# LED-Meter.net
KiCad netlist of a schematic drawn in Altium Designer
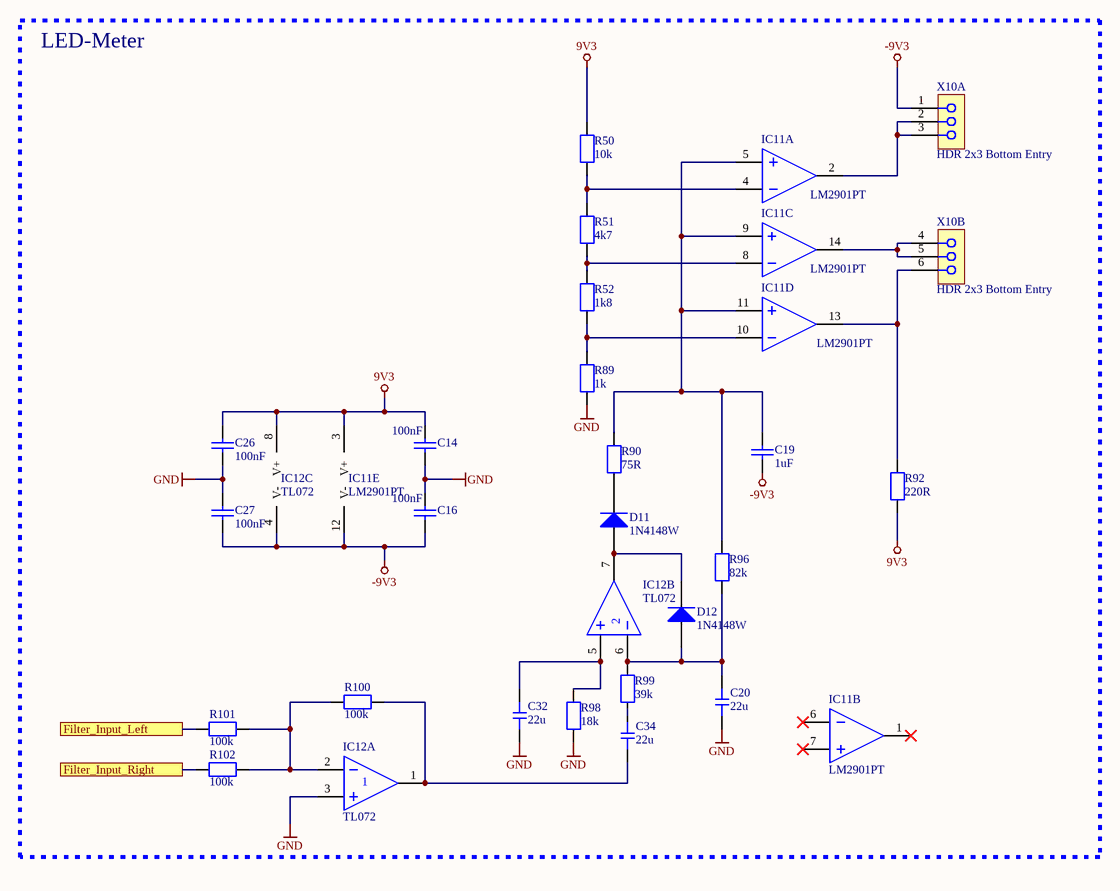
[diagram p0: LED-Meter.SchDoc]

(export (version "E")
  (design (tool "Eeschema 10.0.6"))
  (components
    (comp (ref "C14")
      (value "100nF")
      (footprint "CAPC1608X95N")
      (description "Multilayer Ceramic Capacitors MLCC - SMD/SMT, 100nF")
      (fields
        (field (name "MANUFACTURER") "YAGEO")
        (field (name "MANUFACTURER PART NUMBER") "CC0603KRX7R9BB104")
      )
      (libsource (lib "Caps") (part "CAP_100nF_0603"))
    )
    (comp (ref "C16")
      (value "100nF")
      (footprint "CAPC1608X95N")
      (description "Multilayer Ceramic Capacitors MLCC - SMD/SMT, 100nF")
      (fields
        (field (name "MANUFACTURER") "YAGEO")
        (field (name "MANUFACTURER PART NUMBER") "CC0603KRX7R9BB104")
      )
      (libsource (lib "Caps") (part "CAP_100nF_0603"))
    )
    (comp (ref "C19")
      (value "1uF")
      (footprint "CAPC2012X145N")
      (description "Multilayer Ceramic Capacitors MLCC - SMD/SMT, 1uF")
      (fields
        (field (name "MANUFACTURER") "Samsung Electro-Mechanics")
        (field (name "MANUFACTURER PART NUMBER") "CL21B105KBFNNNE")
      )
      (libsource (lib "Caps") (part "CAP_1uF_0805"))
    )
    (comp (ref "C20")
      (value "22u")
      (footprint "CAPC2012X145N")
      (description "SMD, 22 µF, 35 V, 0805 [metric 2012], ± 20%, X5R, C Series TDK")
      (fields
        (field (name "MANUFACTURER") "TDK")
        (field (name "MANUFACTURER PART NUMBER") "C2012X5R1V226M125AC")
      )
      (libsource (lib "Caps") (part "CAP_22u_35V_0805"))
    )
    (comp (ref "C26")
      (value "100nF")
      (footprint "CAPC1608X95N")
      (description "Multilayer Ceramic Capacitors MLCC - SMD/SMT, 100nF")
      (fields
        (field (name "MANUFACTURER") "YAGEO")
        (field (name "MANUFACTURER PART NUMBER") "CC0603KRX7R9BB104")
      )
      (libsource (lib "Caps") (part "CAP_100nF_0603"))
    )
    (comp (ref "C27")
      (value "100nF")
      (footprint "CAPC1608X95N")
      (description "Multilayer Ceramic Capacitors MLCC - SMD/SMT, 100nF")
      (fields
        (field (name "MANUFACTURER") "YAGEO")
        (field (name "MANUFACTURER PART NUMBER") "CC0603KRX7R9BB104")
      )
      (libsource (lib "Caps") (part "CAP_100nF_0603"))
    )
    (comp (ref "C32")
      (value "22u")
      (footprint "CAPC2012X145N")
      (description "SMD, 22 µF, 35 V, 0805 [metric 2012], ± 20%, X5R, C Series TDK")
      (fields
        (field (name "MANUFACTURER") "TDK")
        (field (name "MANUFACTURER PART NUMBER") "C2012X5R1V226M125AC")
      )
      (libsource (lib "Caps") (part "CAP_22u_35V_0805"))
    )
    (comp (ref "C34")
      (value "22u")
      (footprint "CAPC2012X145N")
      (description "SMD, 22 µF, 35 V, 0805 [metric 2012], ± 20%, X5R, C Series TDK")
      (fields
        (field (name "MANUFACTURER") "TDK")
        (field (name "MANUFACTURER PART NUMBER") "C2012X5R1V226M125AC")
      )
      (libsource (lib "Caps") (part "CAP_22u_35V_0805"))
    )
    (comp (ref "D11")
      (value "1N4148W")
      (footprint "SOD-123")
      (description "75V 150mA 1.25V @ 150mA 4ns SOD-123 Switching Diode RoHS")
      (fields (field (name "MANUFACTURER") "ST(Semtech)"))
      (libsource (lib "Diodes") (part "1N4148W"))
    )
    (comp (ref "D12")
      (value "1N4148W")
      (footprint "SOD-123")
      (description "75V 150mA 1.25V @ 150mA 4ns SOD-123 Switching Diode RoHS")
      (fields (field (name "MANUFACTURER") "ST(Semtech)"))
      (libsource (lib "Diodes") (part "1N4148W"))
    )
    (comp (ref "IC11")
      (value "LM2901PT")
      (footprint "TSOP65P640X105-14N")
      (description "Analog Comparators Lo-Pwr Quad Voltage")
      (fields (field (name "MANUFACTURER") "STMicroelectronics"))
      (libsource (lib "ICs") (part "IC_LM2901PT"))
    )
    (comp (ref "IC12")
      (value "TL072")
      (footprint "SOIC127P600X175-8N")
      (description "Operational Amplifiers - Op Amps Dual JFET Op Amp")
      (fields
        (field (name "MANUFACTURER") "Texas Instruments")
        (field (name "MANUFACTURER PART NUMBER") "TL072CDR")
      )
      (libsource (lib "ICs") (part "IC_TL072"))
    )
    (comp (ref "R50")
      (value "10k")
      (footprint "RESC2012X70N")
      (description "Thick Film Resistors - SMD 1/8watt 10Kohms 1% 100ppm")
      (fields
        (field (name "MANUFACTURER") "Vishay / Dale")
        (field (name "MANUFACTURER PART NUMBER") "CRCW080510K0FKEA")
      )
      (libsource (lib "Resistors") (part "RES_10k_0805"))
    )
    (comp (ref "R51")
      (value "4k7")
      (footprint "RESC2012X70N")
      (description "Thick Film Resistors - SMD 1/8Watt 4.7Kohms 1% Commercial Use")
      (fields
        (field (name "MANUFACTURER") "Vishay / Dale")
        (field (name "MANUFACTURER PART NUMBER") "CRCW08054K70FKEAC")
      )
      (libsource (lib "Resistors") (part "RES_4k7_0805"))
    )
    (comp (ref "R52")
      (value "1k8")
      (footprint "RESC2012X70N")
      (description "Thick Film Resistors - SMD 1/8Watt 1.8Kohms 1% Commercial Use")
      (fields
        (field (name "MANUFACTURER") "Vishay / Dale")
        (field (name "MANUFACTURER PART NUMBER") "CRCW08051K80FKEAC")
      )
      (libsource (lib "Resistors") (part "RES_1k8_0805"))
    )
    (comp (ref "R89")
      (value "1k")
      (footprint "RESC2012X70N")
      (description "Thick Film Resistors - SMD 1/8watt 1Kohms 1% 100ppm")
      (fields
        (field (name "MANUFACTURER") "Vishay / Dale")
        (field (name "MANUFACTURER PART NUMBER") "CRCW08051K00FKEA")
      )
      (libsource (lib "Resistors") (part "RES_1k_0805"))
    )
    (comp (ref "R90")
      (value "75R")
      (footprint "RESC2012X70N")
      (description "Thick Film Resistors - SMD 75 Ohms 125 mW 0805 1%")
      (fields
        (field (name "MANUFACTURER") "YAGEO")
        (field (name "MANUFACTURER PART NUMBER") "RC0805FR-0775RL")
      )
      (libsource (lib "Resistors") (part "RES_75R_0805"))
    )
    (comp (ref "R92")
      (value "220R")
      (footprint "RESC2012X70N")
      (description "Thick Film Resistors - SMD 1/8watt 220ohms 1% 100ppm")
      (fields
        (field (name "MANUFACTURER") "Vishay / Dale")
        (field (name "MANUFACTURER PART NUMBER") "CRCW0805220RFKEA")
      )
      (libsource (lib "Resistors") (part "RES_220R_0805"))
    )
    (comp (ref "R96")
      (value "82k")
      (footprint "RESC2012X70N")
      (description "Thick Film Resistors - SMD 82 kOhms 125 mW 0805 1%")
      (fields
        (field (name "MANUFACTURER") "YAGEO")
        (field (name "MANUFACTURER PART NUMBER") "RC0805FR-0782KL")
      )
      (libsource (lib "Resistors") (part "RES_82k_0805"))
    )
    (comp (ref "R98")
      (value "18k")
      (footprint "RESC2012X70N")
      (description "Thick Film Resistors - SMD 18kOhms 1/8W 0805 1%")
      (fields
        (field (name "MANUFACTURER") "YAGEO")
        (field (name "MANUFACTURER PART NUMBER") "RC0805FR-1018KL")
      )
      (libsource (lib "Resistors") (part "RES_18k_0805"))
    )
    (comp (ref "R99")
      (value "39k")
      (footprint "RESC2012X70N")
      (description "Thick Film Resistors - SMD 39 kOhms 125 mW 0805 1%")
      (fields
        (field (name "MANUFACTURER") "YAGEO")
        (field (name "MANUFACTURER PART NUMBER") "RC0805FR-0739KL")
      )
      (libsource (lib "Resistors") (part "RES_39k_0805"))
    )
    (comp (ref "R100")
      (value "100k")
      (footprint "RESC2012X70N")
      (description "Thick Film Resistors - SMD 1/8watt 100Kohms 1% 100ppm")
      (fields
        (field (name "MANUFACTURER") "Vishay / Dale")
        (field (name "MANUFACTURER PART NUMBER") "CRCW0805100KFKEA")
      )
      (libsource (lib "Resistors") (part "RES_100k_0805"))
    )
    (comp (ref "R101")
      (value "100k")
      (footprint "RESC2012X70N")
      (description "Thick Film Resistors - SMD 1/8watt 100Kohms 1% 100ppm")
      (fields
        (field (name "MANUFACTURER") "Vishay / Dale")
        (field (name "MANUFACTURER PART NUMBER") "CRCW0805100KFKEA")
      )
      (libsource (lib "Resistors") (part "RES_100k_0805"))
    )
    (comp (ref "R102")
      (value "100k")
      (footprint "RESC2012X70N")
      (description "Thick Film Resistors - SMD 1/8watt 100Kohms 1% 100ppm")
      (fields
        (field (name "MANUFACTURER") "Vishay / Dale")
        (field (name "MANUFACTURER PART NUMBER") "CRCW0805100KFKEA")
      )
      (libsource (lib "Resistors") (part "RES_100k_0805"))
    )
    (comp (ref "X10")
      (value "HDR 2x3 Bottom Entry")
      (footprint "613006216921-poti")
      (fields (field (name "MANUFACTURER") "WE") (field (name "MANUFACTURER PART NUMBER") "613004216921"))
      (libsource (lib "Connectors") (part "CON_SOCKET_2x3_Poti"))
    )
  )
  (nets
    (net (code "1") (name "-9V3") (class "Default")
      (node (ref "C16") (pin "1") (pinfunction "1_1") (pintype "passive"))
      (node (ref "C19") (pin "1") (pinfunction "1_1") (pintype "passive"))
      (node (ref "C27") (pin "2") (pinfunction "2_2") (pintype "passive"))
      (node (ref "IC11") (pin "12") (pinfunction "V-_12") (pintype "power_in"))
      (node (ref "IC12") (pin "4") (pinfunction "V-_4") (pintype "power_in"))
      (node (ref "X10") (pin "1") (pinfunction "1_1") (pintype "passive"))
    )
    (net (code "2") (name "/Filter_Input_Left") (class "Default")
      (node (ref "R101") (pin "1") (pinfunction "1_1") (pintype "passive"))
    )
    (net (code "3") (name "/Filter_Input_Right") (class "Default")
      (node (ref "R102") (pin "1") (pinfunction "1_1") (pintype "passive"))
    )
    (net (code "4") (name "9V3") (class "Default")
      (node (ref "C14") (pin "2") (pinfunction "2_2") (pintype "passive"))
      (node (ref "C26") (pin "1") (pinfunction "1_1") (pintype "passive"))
      (node (ref "IC11") (pin "3") (pinfunction "V+_3") (pintype "power_in"))
      (node (ref "IC12") (pin "8") (pinfunction "V+_8") (pintype "power_in"))
      (node (ref "R50") (pin "2") (pinfunction "2_2") (pintype "passive"))
      (node (ref "R92") (pin "1") (pinfunction "1_1") (pintype "passive"))
    )
    (net (code "5") (name "GND") (class "Default")
      (node (ref "C14") (pin "1") (pinfunction "1_1") (pintype "passive"))
      (node (ref "C16") (pin "2") (pinfunction "2_2") (pintype "passive"))
      (node (ref "C20") (pin "1") (pinfunction "1_1") (pintype "passive"))
      (node (ref "C26") (pin "2") (pinfunction "2_2") (pintype "passive"))
      (node (ref "C27") (pin "1") (pinfunction "1_1") (pintype "passive"))
      (node (ref "C32") (pin "1") (pinfunction "1_1") (pintype "passive"))
      (node (ref "IC12") (pin "3") (pinfunction "IN+_3") (pintype "passive"))
      (node (ref "R89") (pin "1") (pinfunction "1_1") (pintype "passive"))
      (node (ref "R98") (pin "1") (pinfunction "1_1") (pintype "passive"))
    )
    (net (code "6") (name "Net-(C34-Pad2)") (class "Default")
      (node (ref "C34") (pin "2") (pinfunction "2_2") (pintype "passive"))
      (node (ref "R99") (pin "1") (pinfunction "1_1") (pintype "passive"))
    )
    (net (code "7") (name "Net-(D11-A)") (class "Default")
      (node (ref "D11") (pin "1") (pinfunction "A_1") (pintype "passive"))
      (node (ref "D12") (pin "2") (pinfunction "K_2") (pintype "passive"))
      (node (ref "IC12") (pin "7") (pinfunction "OUT_7") (pintype "passive"))
    )
    (net (code "8") (name "Net-(D11-K)") (class "Default")
      (node (ref "D11") (pin "2") (pinfunction "K_2") (pintype "passive"))
      (node (ref "R90") (pin "1") (pinfunction "1_1") (pintype "passive"))
    )
    (net (code "9") (name "Net-(D12-A)") (class "Default")
      (node (ref "C20") (pin "2") (pinfunction "2_2") (pintype "passive"))
      (node (ref "D12") (pin "1") (pinfunction "A_1") (pintype "passive"))
      (node (ref "IC12") (pin "6") (pinfunction "IN-_6") (pintype "passive"))
      (node (ref "R96") (pin "1") (pinfunction "1_1") (pintype "passive"))
      (node (ref "R99") (pin "2") (pinfunction "2_2") (pintype "passive"))
    )
    (net (code "10") (name "Net-(IC11A-IN1+)") (class "Default")
      (node (ref "C19") (pin "2") (pinfunction "2_2") (pintype "passive"))
      (node (ref "IC11") (pin "11") (pinfunction "IN4+_11") (pintype "passive"))
      (node (ref "IC11") (pin "5") (pinfunction "IN1+_5") (pintype "passive"))
      (node (ref "IC11") (pin "9") (pinfunction "IN3+_9") (pintype "passive"))
      (node (ref "R90") (pin "2") (pinfunction "2_2") (pintype "passive"))
      (node (ref "R96") (pin "2") (pinfunction "2_2") (pintype "passive"))
    )
    (net (code "11") (name "Net-(IC11A-IN1-)") (class "Default")
      (node (ref "IC11") (pin "4") (pinfunction "IN1-_4") (pintype "passive"))
      (node (ref "R50") (pin "1") (pinfunction "1_1") (pintype "passive"))
      (node (ref "R51") (pin "2") (pinfunction "2_2") (pintype "passive"))
    )
    (net (code "12") (name "Net-(IC11A-OUT_1)") (class "Default")
      (node (ref "IC11") (pin "2") (pinfunction "OUT_1_2") (pintype "passive"))
      (node (ref "X10") (pin "2") (pinfunction "2_2") (pintype "passive"))
      (node (ref "X10") (pin "3") (pinfunction "3_3") (pintype "passive"))
    )
    (net (code "13") (name "Net-(IC11C-IN3-)") (class "Default")
      (node (ref "IC11") (pin "8") (pinfunction "IN3-_8") (pintype "passive"))
      (node (ref "R51") (pin "1") (pinfunction "1_1") (pintype "passive"))
      (node (ref "R52") (pin "2") (pinfunction "2_2") (pintype "passive"))
    )
    (net (code "14") (name "Net-(IC11C-OUT_3)") (class "Default")
      (node (ref "IC11") (pin "14") (pinfunction "OUT_3_14") (pintype "passive"))
      (node (ref "X10") (pin "4") (pinfunction "4_4") (pintype "passive"))
      (node (ref "X10") (pin "5") (pinfunction "5_5") (pintype "passive"))
    )
    (net (code "15") (name "Net-(IC11D-IN4-)") (class "Default")
      (node (ref "IC11") (pin "10") (pinfunction "IN4-_10") (pintype "passive"))
      (node (ref "R52") (pin "1") (pinfunction "1_1") (pintype "passive"))
      (node (ref "R89") (pin "2") (pinfunction "2_2") (pintype "passive"))
    )
    (net (code "16") (name "Net-(IC11D-OUT_4)") (class "Default")
      (node (ref "IC11") (pin "13") (pinfunction "OUT_4_13") (pintype "passive"))
      (node (ref "R92") (pin "2") (pinfunction "2_2") (pintype "passive"))
      (node (ref "X10") (pin "6") (pinfunction "6_6") (pintype "passive"))
    )
    (net (code "17") (name "Net-(IC12A-IN-)") (class "Default")
      (node (ref "IC12") (pin "2") (pinfunction "IN-_2") (pintype "passive"))
      (node (ref "R100") (pin "1") (pinfunction "1_1") (pintype "passive"))
      (node (ref "R101") (pin "2") (pinfunction "2_2") (pintype "passive"))
      (node (ref "R102") (pin "2") (pinfunction "2_2") (pintype "passive"))
    )
    (net (code "18") (name "Net-(IC12A-OUT)") (class "Default")
      (node (ref "C34") (pin "1") (pinfunction "1_1") (pintype "passive"))
      (node (ref "IC12") (pin "1") (pinfunction "OUT_1") (pintype "passive"))
      (node (ref "R100") (pin "2") (pinfunction "2_2") (pintype "passive"))
    )
    (net (code "19") (name "Net-(IC12B-IN+)") (class "Default")
      (node (ref "C32") (pin "2") (pinfunction "2_2") (pintype "passive"))
      (node (ref "IC12") (pin "5") (pinfunction "IN+_5") (pintype "passive"))
      (node (ref "R98") (pin "2") (pinfunction "2_2") (pintype "passive"))
    )
    (net (code "20") (name "unconnected-(IC11B-IN2+-Pad7)") (class "Default")
      (node (ref "IC11") (pin "7") (pinfunction "IN2+_7") (pintype "passive+no_connect"))
    )
    (net (code "21") (name "unconnected-(IC11B-IN2--Pad6)") (class "Default")
      (node (ref "IC11") (pin "6") (pinfunction "IN2-_6") (pintype "passive+no_connect"))
    )
    (net (code "22") (name "unconnected-(IC11B-OUT_2-Pad1)") (class "Default")
      (node (ref "IC11") (pin "1") (pinfunction "OUT_2_1") (pintype "passive+no_connect"))
    )
  )
)
